# dobbelsteen.net
KiCad netlist of a schematic drawn in EAGLE
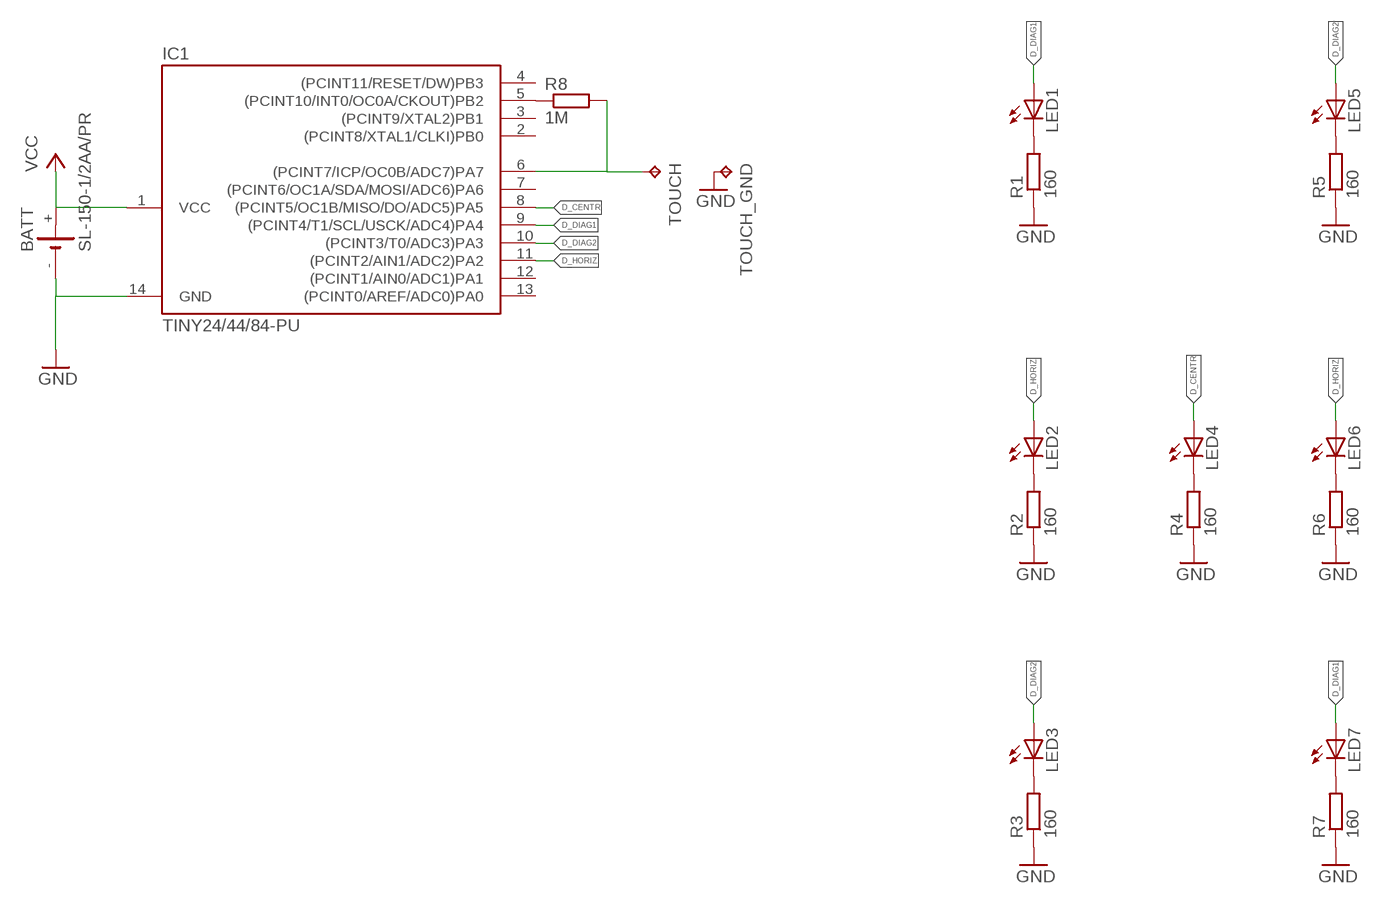
[diagram p0: schematic, sheet 1]

(export (version "E")
  (design (tool "Eeschema 10.0.6"))
  (components
    (comp (ref "BATT")
      (value "SL-150-1/2AA/PR")
      (footprint "eagle-import:SL-150-1_2AA_PR")
      (libsource (lib "eagle-import") (part "SL-150-1/2AA/PR"))
    )
    (comp (ref "IC1")
      (value "TINY24/44/84-PU")
      (footprint "eagle-import:DIL14")
      (libsource (lib "eagle-import") (part "TINY24/44/84-PU"))
    )
    (comp (ref "LED1")
      (value "LED5MM")
      (footprint "eagle-import:LED5MM")
      (libsource (lib "eagle-import") (part "LED5MM"))
    )
    (comp (ref "LED2")
      (value "LED5MM")
      (footprint "eagle-import:LED5MM")
      (libsource (lib "eagle-import") (part "LED5MM"))
    )
    (comp (ref "LED3")
      (value "LED5MM")
      (footprint "eagle-import:LED5MM")
      (libsource (lib "eagle-import") (part "LED5MM"))
    )
    (comp (ref "LED4")
      (value "LED5MM")
      (footprint "eagle-import:LED5MM")
      (libsource (lib "eagle-import") (part "LED5MM"))
    )
    (comp (ref "LED5")
      (value "LED5MM")
      (footprint "eagle-import:LED5MM")
      (libsource (lib "eagle-import") (part "LED5MM"))
    )
    (comp (ref "LED6")
      (value "LED5MM")
      (footprint "eagle-import:LED5MM")
      (libsource (lib "eagle-import") (part "LED5MM"))
    )
    (comp (ref "LED7")
      (value "LED5MM")
      (footprint "eagle-import:LED5MM")
      (libsource (lib "eagle-import") (part "LED5MM"))
    )
    (comp (ref "R1")
      (value "160")
      (footprint "eagle-import:0204_7")
      (libsource (lib "eagle-import") (part "R-EU_0204/7"))
    )
    (comp (ref "R2")
      (value "160")
      (footprint "eagle-import:0204_7")
      (libsource (lib "eagle-import") (part "R-EU_0204/7"))
    )
    (comp (ref "R3")
      (value "160")
      (footprint "eagle-import:0204_7")
      (libsource (lib "eagle-import") (part "R-EU_0204/7"))
    )
    (comp (ref "R4")
      (value "160")
      (footprint "eagle-import:0204_7")
      (libsource (lib "eagle-import") (part "R-EU_0204/7"))
    )
    (comp (ref "R5")
      (value "160")
      (footprint "eagle-import:0204_7")
      (libsource (lib "eagle-import") (part "R-EU_0204/7"))
    )
    (comp (ref "R6")
      (value "160")
      (footprint "eagle-import:0204_7")
      (libsource (lib "eagle-import") (part "R-EU_0204/7"))
    )
    (comp (ref "R7")
      (value "160")
      (footprint "eagle-import:0204_7")
      (libsource (lib "eagle-import") (part "R-EU_0204/7"))
    )
    (comp (ref "R8")
      (value "1M")
      (footprint "eagle-import:0204_7")
      (libsource (lib "eagle-import") (part "R-EU_0204/7"))
    )
    (comp (ref "TOUCH")
      (value "TPPAD1-20Y")
      (footprint "eagle-import:P1-20Y")
      (libsource (lib "eagle-import") (part "TPPAD1-20Y"))
    )
    (comp (ref "TOUCH_GND")
      (value "TPPAD1-20Y")
      (footprint "eagle-import:P1-20Y")
      (libsource (lib "eagle-import") (part "TPPAD1-20Y"))
    )
  )
  (nets
    (net (code "1") (name "D_CENTR") (class "Default")
      (node (ref "IC1") (pin "8") (pinfunction "(PCINT5/OC1B/MISO/DO/ADC5)PA5_8") (pintype "bidirectional"))
      (node (ref "LED4") (pin "A") (pinfunction "A_A") (pintype "passive"))
    )
    (net (code "2") (name "D_DIAG1") (class "Default")
      (node (ref "IC1") (pin "9") (pinfunction "(PCINT4/T1/SCL/USCK/ADC4)PA4_9") (pintype "bidirectional"))
      (node (ref "LED1") (pin "A") (pinfunction "A_A") (pintype "passive"))
      (node (ref "LED7") (pin "A") (pinfunction "A_A") (pintype "passive"))
    )
    (net (code "3") (name "D_DIAG2") (class "Default")
      (node (ref "IC1") (pin "10") (pinfunction "(PCINT3/T0/ADC3)PA3_10") (pintype "bidirectional"))
      (node (ref "LED3") (pin "A") (pinfunction "A_A") (pintype "passive"))
      (node (ref "LED5") (pin "A") (pinfunction "A_A") (pintype "passive"))
    )
    (net (code "4") (name "D_HORIZ") (class "Default")
      (node (ref "IC1") (pin "11") (pinfunction "(PCINT2/AIN1/ADC2)PA2_11") (pintype "bidirectional"))
      (node (ref "LED2") (pin "A") (pinfunction "A_A") (pintype "passive"))
      (node (ref "LED6") (pin "A") (pinfunction "A_A") (pintype "passive"))
    )
    (net (code "5") (name "GND") (class "Default")
      (node (ref "BATT") (pin "-") (pinfunction "-_-") (pintype "passive"))
      (node (ref "IC1") (pin "14") (pinfunction "GND_14") (pintype "power_in"))
      (node (ref "R1") (pin "1") (pinfunction "1_1") (pintype "passive"))
      (node (ref "R2") (pin "1") (pinfunction "1_1") (pintype "passive"))
      (node (ref "R3") (pin "1") (pinfunction "1_1") (pintype "passive"))
      (node (ref "R4") (pin "1") (pinfunction "1_1") (pintype "passive"))
      (node (ref "R5") (pin "1") (pinfunction "1_1") (pintype "passive"))
      (node (ref "R6") (pin "1") (pinfunction "1_1") (pintype "passive"))
      (node (ref "R7") (pin "1") (pinfunction "1_1") (pintype "passive"))
      (node (ref "TOUCH_GND") (pin "TP") (pinfunction "TP_TP") (pintype "input"))
    )
    (net (code "6") (name "Net-(IC1-(PCINT7{slash}ICP{slash}OC0B{slash}ADC7)PA7)") (class "Default")
      (node (ref "IC1") (pin "6") (pinfunction "(PCINT7/ICP/OC0B/ADC7)PA7_6") (pintype "bidirectional"))
      (node (ref "R8") (pin "2") (pinfunction "2_2") (pintype "passive"))
      (node (ref "TOUCH") (pin "TP") (pinfunction "TP_TP") (pintype "input"))
    )
    (net (code "7") (name "Net-(IC1-(PCINT10{slash}INT0{slash}OC0A{slash}CKOUT)PB2)") (class "Default")
      (node (ref "IC1") (pin "5") (pinfunction "(PCINT10/INT0/OC0A/CKOUT)PB2_5") (pintype "bidirectional"))
      (node (ref "R8") (pin "1") (pinfunction "1_1") (pintype "passive"))
    )
    (net (code "8") (name "Net-(LED1-C)") (class "Default")
      (node (ref "LED1") (pin "K") (pinfunction "C_K") (pintype "passive"))
      (node (ref "R1") (pin "2") (pinfunction "2_2") (pintype "passive"))
    )
    (net (code "9") (name "Net-(LED2-C)") (class "Default")
      (node (ref "LED2") (pin "K") (pinfunction "C_K") (pintype "passive"))
      (node (ref "R2") (pin "2") (pinfunction "2_2") (pintype "passive"))
    )
    (net (code "10") (name "Net-(LED3-C)") (class "Default")
      (node (ref "LED3") (pin "K") (pinfunction "C_K") (pintype "passive"))
      (node (ref "R3") (pin "2") (pinfunction "2_2") (pintype "passive"))
    )
    (net (code "11") (name "Net-(LED4-C)") (class "Default")
      (node (ref "LED4") (pin "K") (pinfunction "C_K") (pintype "passive"))
      (node (ref "R4") (pin "2") (pinfunction "2_2") (pintype "passive"))
    )
    (net (code "12") (name "Net-(LED5-C)") (class "Default")
      (node (ref "LED5") (pin "K") (pinfunction "C_K") (pintype "passive"))
      (node (ref "R5") (pin "2") (pinfunction "2_2") (pintype "passive"))
    )
    (net (code "13") (name "Net-(LED6-C)") (class "Default")
      (node (ref "LED6") (pin "K") (pinfunction "C_K") (pintype "passive"))
      (node (ref "R6") (pin "2") (pinfunction "2_2") (pintype "passive"))
    )
    (net (code "14") (name "Net-(LED7-C)") (class "Default")
      (node (ref "LED7") (pin "K") (pinfunction "C_K") (pintype "passive"))
      (node (ref "R7") (pin "2") (pinfunction "2_2") (pintype "passive"))
    )
    (net (code "15") (name "VCC") (class "Default")
      (node (ref "BATT") (pin "+") (pinfunction "+_+") (pintype "passive"))
      (node (ref "IC1") (pin "1") (pinfunction "VCC_1") (pintype "power_in"))
    )
    (net (code "16") (name "unconnected-(IC1-(PCINT0{slash}AREF{slash}ADC0)PA0-Pad13)") (class "Default")
      (node (ref "IC1") (pin "13") (pinfunction "(PCINT0/AREF/ADC0)PA0_13") (pintype "bidirectional"))
    )
    (net (code "17") (name "unconnected-(IC1-(PCINT1{slash}AIN0{slash}ADC1)PA1-Pad12)") (class "Default")
      (node (ref "IC1") (pin "12") (pinfunction "(PCINT1/AIN0/ADC1)PA1_12") (pintype "bidirectional"))
    )
    (net (code "18") (name "unconnected-(IC1-(PCINT6{slash}OC1A{slash}SDA{slash}MOSI{slash}ADC6)PA6-Pad7)") (class "Default")
      (node (ref "IC1") (pin "7") (pinfunction "(PCINT6/OC1A/SDA/MOSI/ADC6)PA6_7") (pintype "bidirectional"))
    )
    (net (code "19") (name "unconnected-(IC1-(PCINT8{slash}XTAL1{slash}CLKI)PB0-Pad2)") (class "Default")
      (node (ref "IC1") (pin "2") (pinfunction "(PCINT8/XTAL1/CLKI)PB0_2") (pintype "bidirectional"))
    )
    (net (code "20") (name "unconnected-(IC1-(PCINT9{slash}XTAL2)PB1-Pad3)") (class "Default")
      (node (ref "IC1") (pin "3") (pinfunction "(PCINT9/XTAL2)PB1_3") (pintype "bidirectional"))
    )
    (net (code "21") (name "unconnected-(IC1-(PCINT11{slash}RESET{slash}DW)PB3-Pad4)") (class "Default")
      (node (ref "IC1") (pin "4") (pinfunction "(PCINT11/RESET/DW)PB3_4") (pintype "bidirectional"))
    )
  )
)
